# UPS_BOARD.net
KiCad netlist of a schematic drawn in EAGLE
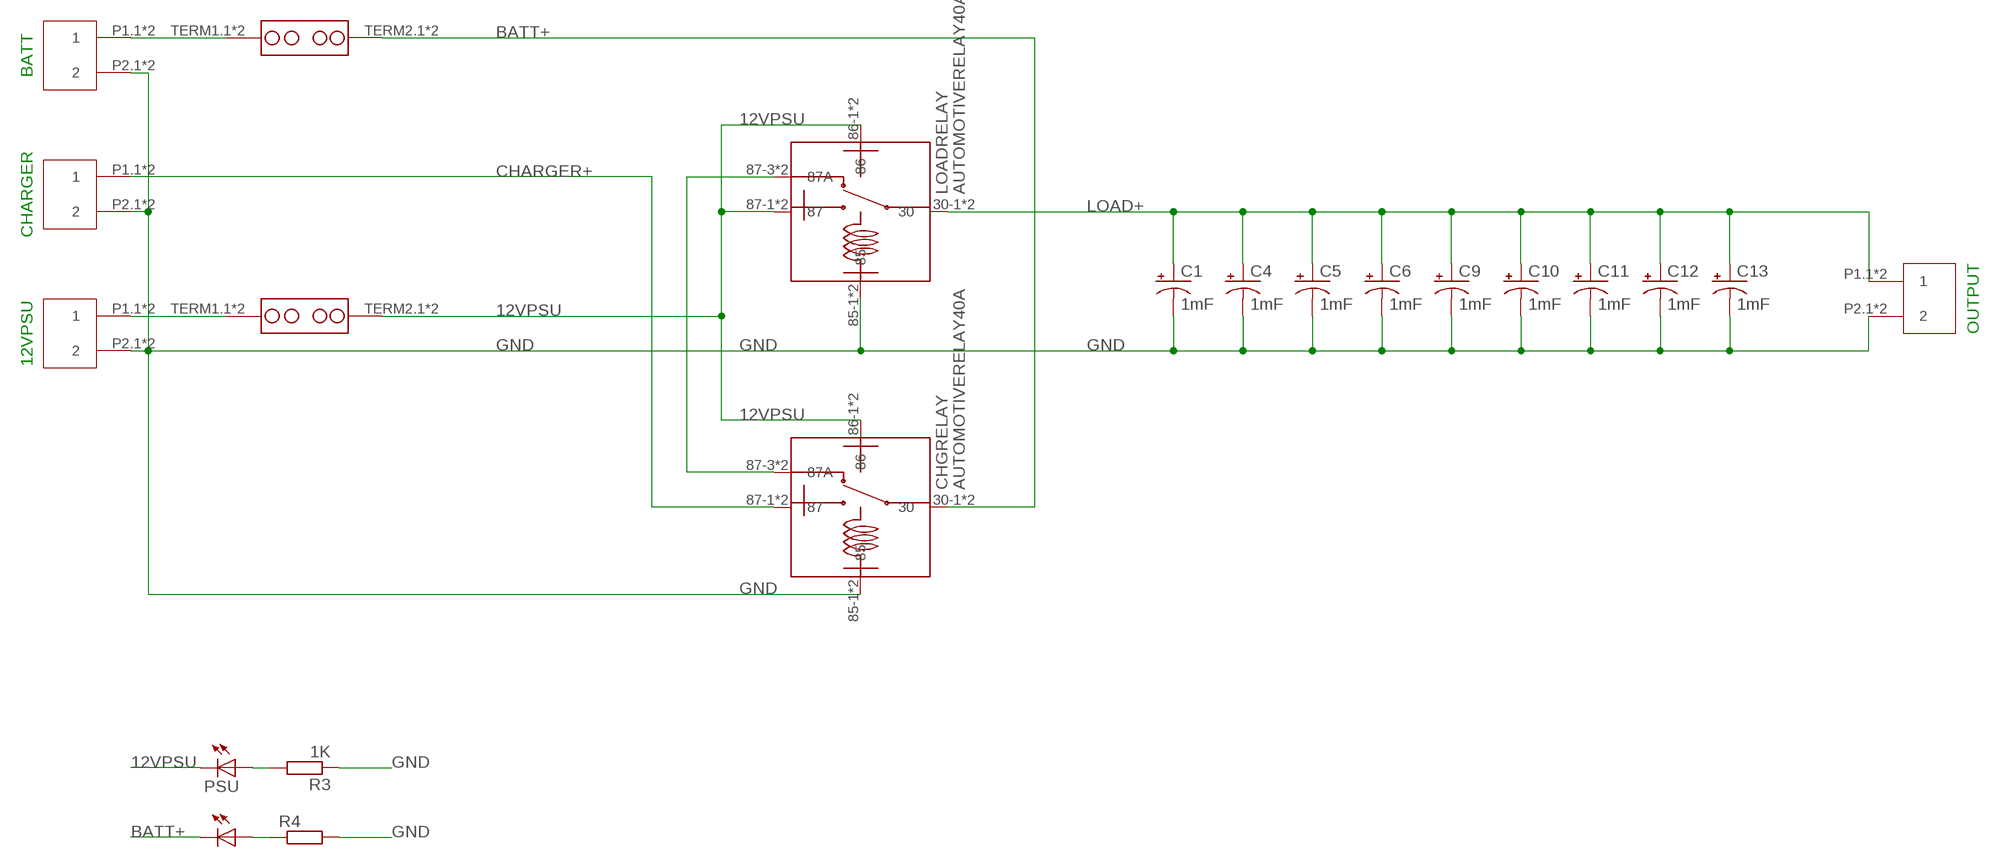
[diagram p0: schematic, sheet 1]

(export (version "E")
  (design (tool "Eeschema 10.0.6"))
  (components
    (comp (ref "BATT")
      (value "LED5MM")
      (footprint "eagle-import:LED5MM")
      (libsource (lib "eagle-import") (part "LED5MM"))
    )
    (comp (ref "C1")
      (value "1mF")
      (footprint "eagle-import:CPOL-RADIAL-5MM-10MM")
      (libsource (lib "eagle-import") (part "1000UF-RADIAL-5MM-25V-20%"))
    )
    (comp (ref "C4")
      (value "1mF")
      (footprint "eagle-import:CPOL-RADIAL-5MM-10MM")
      (libsource (lib "eagle-import") (part "1000UF-RADIAL-5MM-25V-20%"))
    )
    (comp (ref "C5")
      (value "1mF")
      (footprint "eagle-import:CPOL-RADIAL-5MM-10MM")
      (libsource (lib "eagle-import") (part "1000UF-RADIAL-5MM-25V-20%"))
    )
    (comp (ref "C6")
      (value "1mF")
      (footprint "eagle-import:CPOL-RADIAL-5MM-10MM")
      (libsource (lib "eagle-import") (part "1000UF-RADIAL-5MM-25V-20%"))
    )
    (comp (ref "C9")
      (value "1mF")
      (footprint "eagle-import:CPOL-RADIAL-5MM-10MM")
      (libsource (lib "eagle-import") (part "1000UF-RADIAL-5MM-25V-20%"))
    )
    (comp (ref "C10")
      (value "1mF")
      (footprint "eagle-import:CPOL-RADIAL-5MM-10MM")
      (libsource (lib "eagle-import") (part "1000UF-RADIAL-5MM-25V-20%"))
    )
    (comp (ref "C11")
      (value "1mF")
      (footprint "eagle-import:CPOL-RADIAL-5MM-10MM")
      (libsource (lib "eagle-import") (part "1000UF-RADIAL-5MM-25V-20%"))
    )
    (comp (ref "C12")
      (value "1mF")
      (footprint "eagle-import:CPOL-RADIAL-5MM-10MM")
      (libsource (lib "eagle-import") (part "1000UF-RADIAL-5MM-25V-20%"))
    )
    (comp (ref "C13")
      (value "1mF")
      (footprint "eagle-import:CPOL-RADIAL-5MM-10MM")
      (libsource (lib "eagle-import") (part "1000UF-RADIAL-5MM-25V-20%"))
    )
    (comp (ref "CHARGER2")
      (value "BARRIERTERMINAL")
      (footprint "eagle-import:BARRIERTERMINAL")
      (libsource (lib "eagle-import") (part "BARRIERTERMINAL"))
    )
    (comp (ref "CHARGER3")
      (value "BARRIERTERMINAL")
      (footprint "eagle-import:BARRIERTERMINAL")
      (libsource (lib "eagle-import") (part "BARRIERTERMINAL"))
    )
    (comp (ref "CHARGER4")
      (value "BARRIERTERMINAL")
      (footprint "eagle-import:BARRIERTERMINAL")
      (libsource (lib "eagle-import") (part "BARRIERTERMINAL"))
    )
    (comp (ref "CHARGER5")
      (value "BARRIERTERMINAL")
      (footprint "eagle-import:BARRIERTERMINAL")
      (libsource (lib "eagle-import") (part "BARRIERTERMINAL"))
    )
    (comp (ref "CHGRELAY")
      (value "AUTOMOTIVERELAY40A")
      (footprint "eagle-import:AUTOMOTIVERELAY40A")
      (libsource (lib "eagle-import") (part "AUTOMOTIVERELAY40A"))
    )
    (comp (ref "LOADRELAY")
      (value "AUTOMOTIVERELAY40A")
      (footprint "eagle-import:AUTOMOTIVERELAY40A")
      (libsource (lib "eagle-import") (part "AUTOMOTIVERELAY40A"))
    )
    (comp (ref "PSU")
      (value "LED5MM")
      (footprint "eagle-import:LED5MM")
      (libsource (lib "eagle-import") (part "LED5MM"))
    )
    (comp (ref "R3")
      (value "1K")
      (footprint "eagle-import:0204_7")
      (libsource (lib "eagle-import") (part "R-EU_0204/7"))
    )
    (comp (ref "R4")
      (value "1K")
      (footprint "eagle-import:0204_7")
      (libsource (lib "eagle-import") (part "R-EU_0204/7"))
    )
    (comp (ref "U$15")
      (value "ATQ-FUSE")
      (footprint "eagle-import:ATQ-FUSE")
      (libsource (lib "eagle-import") (part "ATQ-FUSE"))
    )
    (comp (ref "U$17")
      (value "ATQ-FUSE")
      (footprint "eagle-import:ATQ-FUSE")
      (libsource (lib "eagle-import") (part "ATQ-FUSE"))
    )
  )
  (nets
    (net (code "1") (name "/12VPSU") (class "Default")
      (node (ref "CHGRELAY") (pin "86-1") (pinfunction "86_86-1") (pintype "bidirectional"))
      (node (ref "CHGRELAY") (pin "86-2") (pinfunction "86_86-2") (pintype "bidirectional"))
      (node (ref "LOADRELAY") (pin "86-1") (pinfunction "86_86-1") (pintype "bidirectional"))
      (node (ref "LOADRELAY") (pin "86-2") (pinfunction "86_86-2") (pintype "bidirectional"))
      (node (ref "LOADRELAY") (pin "87-1") (pinfunction "87_87-1") (pintype "bidirectional"))
      (node (ref "LOADRELAY") (pin "87-2") (pinfunction "87_87-2") (pintype "bidirectional"))
      (node (ref "PSU") (pin "K") (pinfunction "C_K") (pintype "passive"))
      (node (ref "U$17") (pin "TERM2.1") (pinfunction "P$2_TERM2.1") (pintype "bidirectional"))
      (node (ref "U$17") (pin "TERM2.2") (pinfunction "P$2_TERM2.2") (pintype "bidirectional"))
    )
    (net (code "2") (name "/BATT+") (class "Default")
      (node (ref "BATT") (pin "K") (pinfunction "C_K") (pintype "passive"))
      (node (ref "CHGRELAY") (pin "30-1") (pinfunction "30_30-1") (pintype "bidirectional"))
      (node (ref "CHGRELAY") (pin "30-2") (pinfunction "30_30-2") (pintype "bidirectional"))
      (node (ref "U$15") (pin "TERM2.1") (pinfunction "P$2_TERM2.1") (pintype "bidirectional"))
      (node (ref "U$15") (pin "TERM2.2") (pinfunction "P$2_TERM2.2") (pintype "bidirectional"))
    )
    (net (code "3") (name "/CHARGER+") (class "Default")
      (node (ref "CHARGER5") (pin "P1.1") (pinfunction "1_P1.1") (pintype "bidirectional"))
      (node (ref "CHARGER5") (pin "P1.2") (pinfunction "1_P1.2") (pintype "bidirectional"))
      (node (ref "CHGRELAY") (pin "87-1") (pinfunction "87_87-1") (pintype "bidirectional"))
      (node (ref "CHGRELAY") (pin "87-2") (pinfunction "87_87-2") (pintype "bidirectional"))
    )
    (net (code "4") (name "/GND") (class "Default")
      (node (ref "C1") (pin "-") (pinfunction "-_-") (pintype "passive"))
      (node (ref "C10") (pin "-") (pinfunction "-_-") (pintype "passive"))
      (node (ref "C11") (pin "-") (pinfunction "-_-") (pintype "passive"))
      (node (ref "C12") (pin "-") (pinfunction "-_-") (pintype "passive"))
      (node (ref "C13") (pin "-") (pinfunction "-_-") (pintype "passive"))
      (node (ref "C4") (pin "-") (pinfunction "-_-") (pintype "passive"))
      (node (ref "C5") (pin "-") (pinfunction "-_-") (pintype "passive"))
      (node (ref "C6") (pin "-") (pinfunction "-_-") (pintype "passive"))
      (node (ref "C9") (pin "-") (pinfunction "-_-") (pintype "passive"))
      (node (ref "CHARGER2") (pin "P2.1") (pinfunction "2_P2.1") (pintype "bidirectional"))
      (node (ref "CHARGER2") (pin "P2.2") (pinfunction "2_P2.2") (pintype "bidirectional"))
      (node (ref "CHARGER3") (pin "P2.1") (pinfunction "2_P2.1") (pintype "bidirectional"))
      (node (ref "CHARGER3") (pin "P2.2") (pinfunction "2_P2.2") (pintype "bidirectional"))
      (node (ref "CHARGER4") (pin "P2.1") (pinfunction "2_P2.1") (pintype "bidirectional"))
      (node (ref "CHARGER4") (pin "P2.2") (pinfunction "2_P2.2") (pintype "bidirectional"))
      (node (ref "CHARGER5") (pin "P2.1") (pinfunction "2_P2.1") (pintype "bidirectional"))
      (node (ref "CHARGER5") (pin "P2.2") (pinfunction "2_P2.2") (pintype "bidirectional"))
      (node (ref "CHGRELAY") (pin "85-1") (pinfunction "85_85-1") (pintype "bidirectional"))
      (node (ref "CHGRELAY") (pin "85-2") (pinfunction "85_85-2") (pintype "bidirectional"))
      (node (ref "LOADRELAY") (pin "85-1") (pinfunction "85_85-1") (pintype "bidirectional"))
      (node (ref "LOADRELAY") (pin "85-2") (pinfunction "85_85-2") (pintype "bidirectional"))
      (node (ref "R3") (pin "1") (pinfunction "1_1") (pintype "passive"))
      (node (ref "R4") (pin "2") (pinfunction "2_2") (pintype "passive"))
    )
    (net (code "5") (name "/LOAD+") (class "Default")
      (node (ref "C1") (pin "+") (pinfunction "+_+") (pintype "passive"))
      (node (ref "C10") (pin "+") (pinfunction "+_+") (pintype "passive"))
      (node (ref "C11") (pin "+") (pinfunction "+_+") (pintype "passive"))
      (node (ref "C12") (pin "+") (pinfunction "+_+") (pintype "passive"))
      (node (ref "C13") (pin "+") (pinfunction "+_+") (pintype "passive"))
      (node (ref "C4") (pin "+") (pinfunction "+_+") (pintype "passive"))
      (node (ref "C5") (pin "+") (pinfunction "+_+") (pintype "passive"))
      (node (ref "C6") (pin "+") (pinfunction "+_+") (pintype "passive"))
      (node (ref "C9") (pin "+") (pinfunction "+_+") (pintype "passive"))
      (node (ref "CHARGER4") (pin "P1.1") (pinfunction "1_P1.1") (pintype "bidirectional"))
      (node (ref "CHARGER4") (pin "P1.2") (pinfunction "1_P1.2") (pintype "bidirectional"))
      (node (ref "LOADRELAY") (pin "30-1") (pinfunction "30_30-1") (pintype "bidirectional"))
      (node (ref "LOADRELAY") (pin "30-2") (pinfunction "30_30-2") (pintype "bidirectional"))
    )
    (net (code "6") (name "Net-(BATT-PadA)") (class "Default")
      (node (ref "BATT") (pin "A") (pinfunction "A_A") (pintype "passive"))
      (node (ref "R4") (pin "1") (pinfunction "1_1") (pintype "passive"))
    )
    (net (code "7") (name "Net-(CHARGER2-1-PadP1.1)") (class "Default")
      (node (ref "CHARGER2") (pin "P1.1") (pinfunction "1_P1.1") (pintype "bidirectional"))
      (node (ref "CHARGER2") (pin "P1.2") (pinfunction "1_P1.2") (pintype "bidirectional"))
      (node (ref "U$15") (pin "TERM1.1") (pinfunction "P$1_TERM1.1") (pintype "bidirectional"))
      (node (ref "U$15") (pin "TERM1.2") (pinfunction "P$1_TERM1.2") (pintype "bidirectional"))
    )
    (net (code "8") (name "Net-(CHARGER3-1-PadP1.1)") (class "Default")
      (node (ref "CHARGER3") (pin "P1.1") (pinfunction "1_P1.1") (pintype "bidirectional"))
      (node (ref "CHARGER3") (pin "P1.2") (pinfunction "1_P1.2") (pintype "bidirectional"))
      (node (ref "U$17") (pin "TERM1.1") (pinfunction "P$1_TERM1.1") (pintype "bidirectional"))
      (node (ref "U$17") (pin "TERM1.2") (pinfunction "P$1_TERM1.2") (pintype "bidirectional"))
    )
    (net (code "9") (name "Net-(CHGRELAY-87A-Pad87-3)") (class "Default")
      (node (ref "CHGRELAY") (pin "87-3") (pinfunction "87A_87-3") (pintype "bidirectional"))
      (node (ref "CHGRELAY") (pin "87-4") (pinfunction "87A_87-4") (pintype "bidirectional"))
      (node (ref "LOADRELAY") (pin "87-3") (pinfunction "87A_87-3") (pintype "bidirectional"))
      (node (ref "LOADRELAY") (pin "87-4") (pinfunction "87A_87-4") (pintype "bidirectional"))
    )
    (net (code "10") (name "Net-(PSU-PadA)") (class "Default")
      (node (ref "PSU") (pin "A") (pinfunction "A_A") (pintype "passive"))
      (node (ref "R3") (pin "2") (pinfunction "2_2") (pintype "passive"))
    )
  )
)
